# LCD.net
KiCad netlist of a schematic drawn in Altium Designer
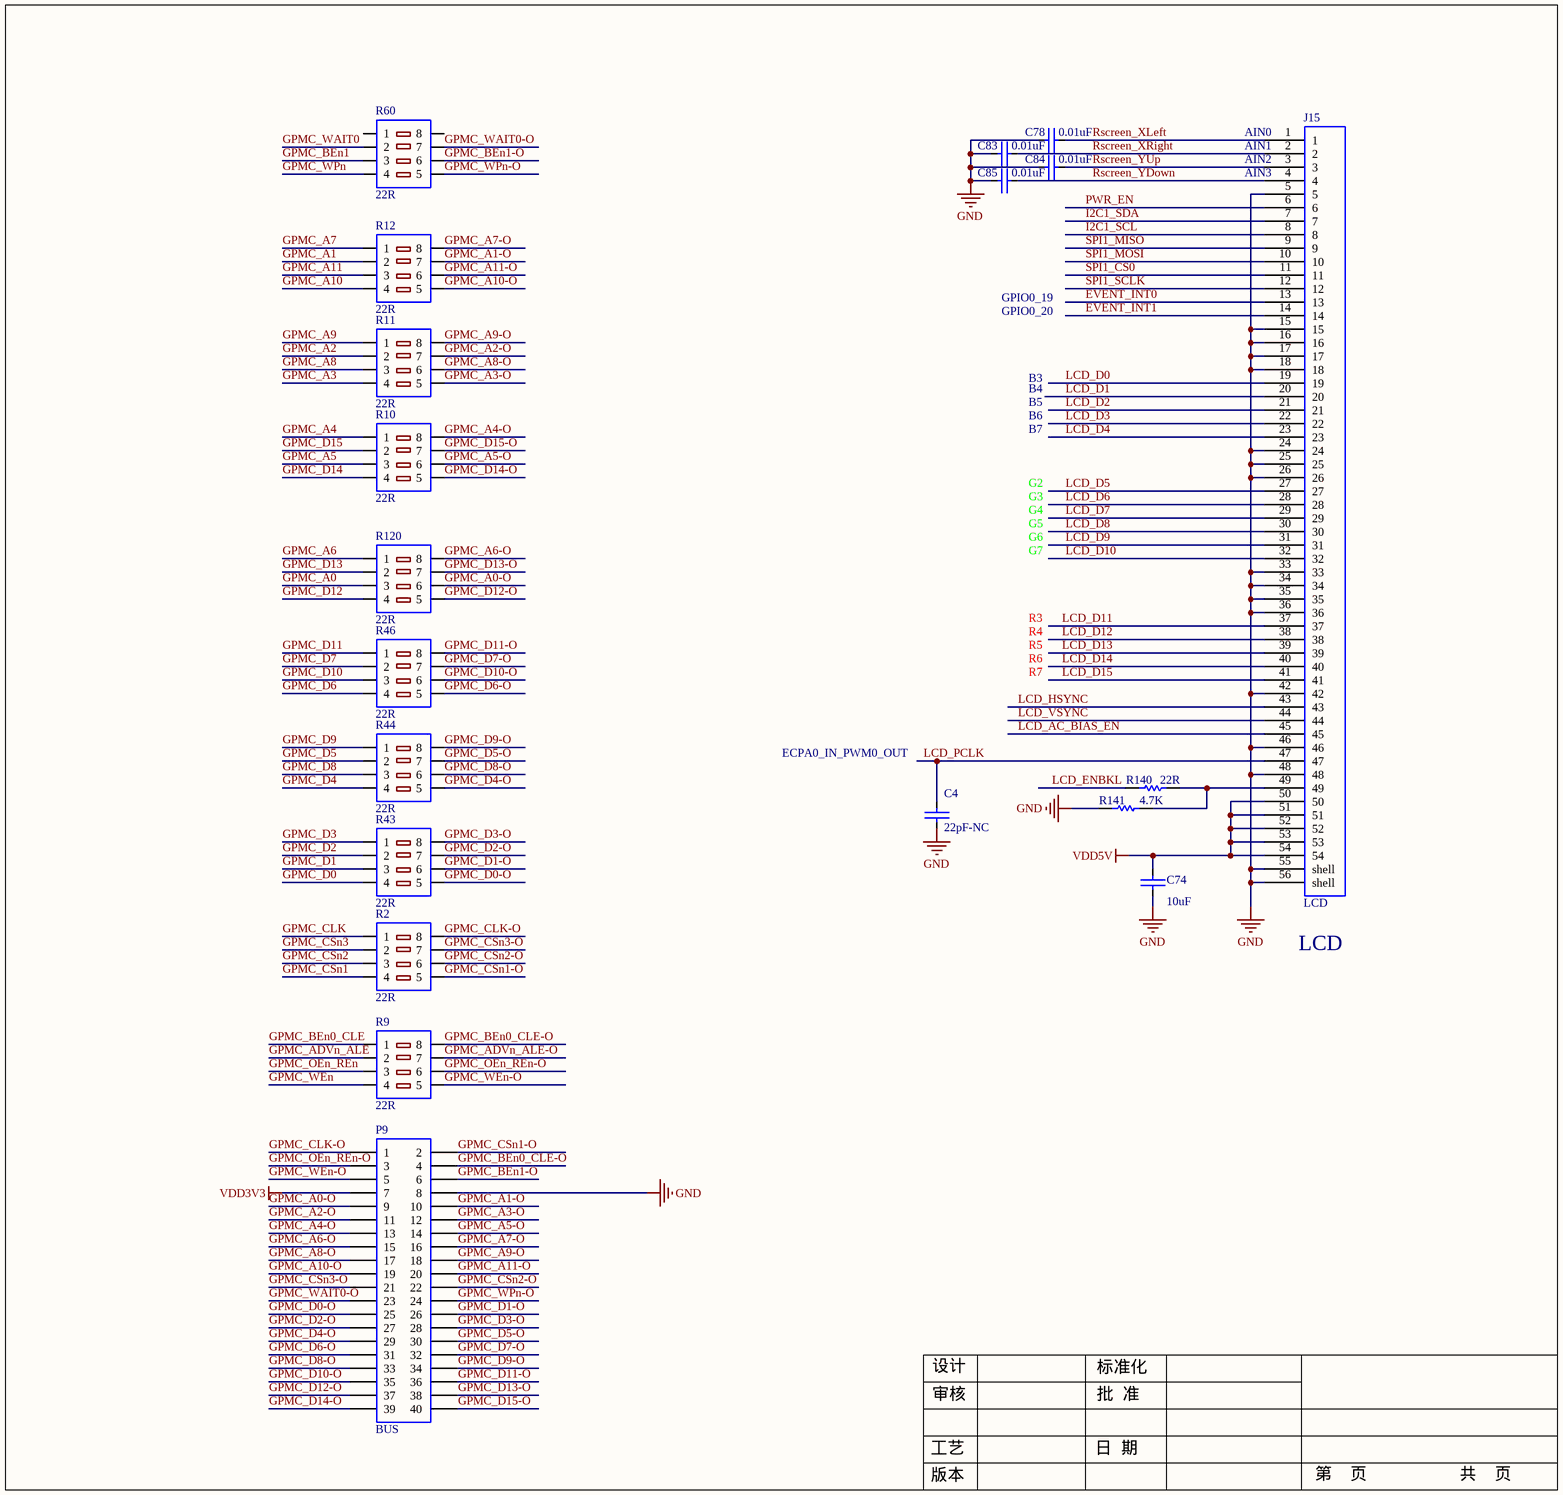
[diagram p0: LCD.SchDoc]

(export (version "E")
  (design (tool "Eeschema 10.0.6"))
  (components
    (comp (ref "C4") (value "22pF-NC") (footprint "C0603_M1608") (libsource (lib "OK335xD") (part "CAP_1")))
    (comp (ref "C74") (value "10uF") (footprint "C0603_M1608") (libsource (lib "OK335xD") (part "CAP_1")))
    (comp (ref "C78") (value "0.01uF") (footprint "C0603_M1608") (libsource (lib "OK335xD") (part "CAP_1")))
    (comp (ref "C83") (value "0.01uF") (footprint "C0603_M1608") (libsource (lib "OK335xD") (part "CAP_1")))
    (comp (ref "C84") (value "0.01uF") (footprint "C0603_M1608") (libsource (lib "OK335xD") (part "CAP_1")))
    (comp (ref "C85") (value "0.01uF") (footprint "C0603_M1608") (libsource (lib "OK335xD") (part "CAP_1")))
    (comp (ref "J15") (value "LCD") (footprint "FPC54") (libsource (lib "OK335xD") (part "FPC54")))
    (comp (ref "P9")
      (value "BUS")
      (description "Header, 20-Pin, Dual row")
      (fields (field (name "PUBLISHER") "Altium Limited"))
      (libsource (lib "OK335xD") (part "Header 20X2"))
    )
    (comp (ref "R2") (value "22R") (footprint "R0603-8P4R") (libsource (lib "OK335xD") (part "8P4R")))
    (comp (ref "R9") (value "22R") (footprint "R0603-8P4R") (libsource (lib "OK335xD") (part "8P4R")))
    (comp (ref "R10") (value "22R") (footprint "R0603-8P4R") (libsource (lib "OK335xD") (part "8P4R")))
    (comp (ref "R11") (value "22R") (footprint "R0603-8P4R") (libsource (lib "OK335xD") (part "8P4R")))
    (comp (ref "R12") (value "22R") (footprint "R0603-8P4R") (libsource (lib "OK335xD") (part "8P4R")))
    (comp (ref "R43") (value "22R") (footprint "R0603-8P4R") (libsource (lib "OK335xD") (part "8P4R")))
    (comp (ref "R44") (value "22R") (footprint "R0603-8P4R") (libsource (lib "OK335xD") (part "8P4R")))
    (comp (ref "R46") (value "22R") (footprint "R0603-8P4R") (libsource (lib "OK335xD") (part "8P4R")))
    (comp (ref "R60") (value "22R") (footprint "R0603-8P4R") (libsource (lib "OK335xD") (part "8P4R")))
    (comp (ref "R120") (value "22R") (footprint "R0603-8P4R") (libsource (lib "OK335xD") (part "8P4R")))
    (comp (ref "R140")
      (value "22R")
      (footprint "R0603_M1608")
      (description "R0603")
      (fields (field (name "PUBLISHER") "Altium Limited"))
      (libsource (lib "Miscellaneous Devices") (part "Res1"))
    )
    (comp (ref "R141")
      (value "4.7K")
      (footprint "R0603_M1608")
      (description "R0603")
      (fields (field (name "PUBLISHER") "Altium Limited"))
      (libsource (lib "Miscellaneous Devices") (part "Res1"))
    )
  )
  (nets
    (net (code "1") (name "/EVENT_INT0") (class "Default")
      (node (ref "J15") (pin "13") (pinfunction "13_13") (pintype "passive"))
    )
    (net (code "2") (name "/EVENT_INT1") (class "Default")
      (node (ref "J15") (pin "14") (pinfunction "14_14") (pintype "passive"))
    )
    (net (code "3") (name "/GPMC_A0") (class "Default")
      (node (ref "R120") (pin "3") (pinfunction "3_3") (pintype "passive"))
    )
    (net (code "4") (name "/GPMC_A0-O") (class "Default")
      (node (ref "P9") (pin "9") (pinfunction "9_9") (pintype "passive"))
      (node (ref "R120") (pin "6") (pinfunction "6_6") (pintype "passive"))
    )
    (net (code "5") (name "/GPMC_A1") (class "Default")
      (node (ref "R12") (pin "2") (pinfunction "2_2") (pintype "passive"))
    )
    (net (code "6") (name "/GPMC_A1-O") (class "Default")
      (node (ref "P9") (pin "10") (pinfunction "10_10") (pintype "passive"))
      (node (ref "R12") (pin "7") (pinfunction "7_7") (pintype "passive"))
    )
    (net (code "7") (name "/GPMC_A2") (class "Default")
      (node (ref "R11") (pin "2") (pinfunction "2_2") (pintype "passive"))
    )
    (net (code "8") (name "/GPMC_A2-O") (class "Default")
      (node (ref "P9") (pin "11") (pinfunction "11_11") (pintype "passive"))
      (node (ref "R11") (pin "7") (pinfunction "7_7") (pintype "passive"))
    )
    (net (code "9") (name "/GPMC_A3") (class "Default")
      (node (ref "R11") (pin "4") (pinfunction "4_4") (pintype "passive"))
    )
    (net (code "10") (name "/GPMC_A3-O") (class "Default")
      (node (ref "P9") (pin "12") (pinfunction "12_12") (pintype "passive"))
      (node (ref "R11") (pin "5") (pinfunction "5_5") (pintype "passive"))
    )
    (net (code "11") (name "/GPMC_A4") (class "Default")
      (node (ref "R10") (pin "1") (pinfunction "1_1") (pintype "passive"))
    )
    (net (code "12") (name "/GPMC_A4-O") (class "Default")
      (node (ref "P9") (pin "13") (pinfunction "13_13") (pintype "passive"))
      (node (ref "R10") (pin "8") (pinfunction "8_8") (pintype "passive"))
    )
    (net (code "13") (name "/GPMC_A5") (class "Default")
      (node (ref "R10") (pin "3") (pinfunction "3_3") (pintype "passive"))
    )
    (net (code "14") (name "/GPMC_A5-O") (class "Default")
      (node (ref "P9") (pin "14") (pinfunction "14_14") (pintype "passive"))
      (node (ref "R10") (pin "6") (pinfunction "6_6") (pintype "passive"))
    )
    (net (code "15") (name "/GPMC_A6") (class "Default")
      (node (ref "R120") (pin "1") (pinfunction "1_1") (pintype "passive"))
    )
    (net (code "16") (name "/GPMC_A6-O") (class "Default")
      (node (ref "P9") (pin "15") (pinfunction "15_15") (pintype "passive"))
      (node (ref "R120") (pin "8") (pinfunction "8_8") (pintype "passive"))
    )
    (net (code "17") (name "/GPMC_A7") (class "Default")
      (node (ref "R12") (pin "1") (pinfunction "1_1") (pintype "passive"))
    )
    (net (code "18") (name "/GPMC_A7-O") (class "Default")
      (node (ref "P9") (pin "16") (pinfunction "16_16") (pintype "passive"))
      (node (ref "R12") (pin "8") (pinfunction "8_8") (pintype "passive"))
    )
    (net (code "19") (name "/GPMC_A8") (class "Default")
      (node (ref "R11") (pin "3") (pinfunction "3_3") (pintype "passive"))
    )
    (net (code "20") (name "/GPMC_A8-O") (class "Default")
      (node (ref "P9") (pin "17") (pinfunction "17_17") (pintype "passive"))
      (node (ref "R11") (pin "6") (pinfunction "6_6") (pintype "passive"))
    )
    (net (code "21") (name "/GPMC_A9") (class "Default")
      (node (ref "R11") (pin "1") (pinfunction "1_1") (pintype "passive"))
    )
    (net (code "22") (name "/GPMC_A9-O") (class "Default")
      (node (ref "P9") (pin "18") (pinfunction "18_18") (pintype "passive"))
      (node (ref "R11") (pin "8") (pinfunction "8_8") (pintype "passive"))
    )
    (net (code "23") (name "/GPMC_A10") (class "Default")
      (node (ref "R12") (pin "4") (pinfunction "4_4") (pintype "passive"))
    )
    (net (code "24") (name "/GPMC_A10-O") (class "Default")
      (node (ref "P9") (pin "19") (pinfunction "19_19") (pintype "passive"))
      (node (ref "R12") (pin "5") (pinfunction "5_5") (pintype "passive"))
    )
    (net (code "25") (name "/GPMC_A11") (class "Default")
      (node (ref "R12") (pin "3") (pinfunction "3_3") (pintype "passive"))
    )
    (net (code "26") (name "/GPMC_A11-O") (class "Default")
      (node (ref "P9") (pin "20") (pinfunction "20_20") (pintype "passive"))
      (node (ref "R12") (pin "6") (pinfunction "6_6") (pintype "passive"))
    )
    (net (code "27") (name "/GPMC_ADVn_ALE") (class "Default")
      (node (ref "R9") (pin "2") (pinfunction "2_2") (pintype "passive"))
    )
    (net (code "28") (name "/GPMC_ADVn_ALE-O") (class "Default")
      (node (ref "R9") (pin "7") (pinfunction "7_7") (pintype "passive"))
    )
    (net (code "29") (name "/GPMC_BEn0_CLE") (class "Default")
      (node (ref "R9") (pin "1") (pinfunction "1_1") (pintype "passive"))
    )
    (net (code "30") (name "/GPMC_BEn0_CLE-O") (class "Default")
      (node (ref "P9") (pin "4") (pinfunction "4_4") (pintype "passive"))
      (node (ref "R9") (pin "8") (pinfunction "8_8") (pintype "passive"))
    )
    (net (code "31") (name "/GPMC_BEn1") (class "Default")
      (node (ref "R60") (pin "3") (pinfunction "3_3") (pintype "passive"))
    )
    (net (code "32") (name "/GPMC_BEn1-O") (class "Default")
      (node (ref "P9") (pin "6") (pinfunction "6_6") (pintype "passive"))
      (node (ref "R60") (pin "6") (pinfunction "6_6") (pintype "passive"))
    )
    (net (code "33") (name "/GPMC_CLK") (class "Default")
      (node (ref "R2") (pin "1") (pinfunction "1_1") (pintype "passive"))
    )
    (net (code "34") (name "/GPMC_CLK-O") (class "Default")
      (node (ref "P9") (pin "1") (pinfunction "1_1") (pintype "passive"))
      (node (ref "R2") (pin "8") (pinfunction "8_8") (pintype "passive"))
    )
    (net (code "35") (name "/GPMC_CSn1") (class "Default")
      (node (ref "R2") (pin "4") (pinfunction "4_4") (pintype "passive"))
    )
    (net (code "36") (name "/GPMC_CSn1-O") (class "Default")
      (node (ref "P9") (pin "2") (pinfunction "2_2") (pintype "passive"))
      (node (ref "R2") (pin "5") (pinfunction "5_5") (pintype "passive"))
    )
    (net (code "37") (name "/GPMC_CSn2") (class "Default")
      (node (ref "R2") (pin "3") (pinfunction "3_3") (pintype "passive"))
    )
    (net (code "38") (name "/GPMC_CSn2-O") (class "Default")
      (node (ref "P9") (pin "22") (pinfunction "22_22") (pintype "passive"))
      (node (ref "R2") (pin "6") (pinfunction "6_6") (pintype "passive"))
    )
    (net (code "39") (name "/GPMC_CSn3") (class "Default")
      (node (ref "R2") (pin "2") (pinfunction "2_2") (pintype "passive"))
    )
    (net (code "40") (name "/GPMC_CSn3-O") (class "Default")
      (node (ref "P9") (pin "21") (pinfunction "21_21") (pintype "passive"))
      (node (ref "R2") (pin "7") (pinfunction "7_7") (pintype "passive"))
    )
    (net (code "41") (name "/GPMC_D0") (class "Default")
      (node (ref "R43") (pin "4") (pinfunction "4_4") (pintype "passive"))
    )
    (net (code "42") (name "/GPMC_D0-O") (class "Default")
      (node (ref "P9") (pin "25") (pinfunction "25_25") (pintype "passive"))
      (node (ref "R43") (pin "5") (pinfunction "5_5") (pintype "passive"))
    )
    (net (code "43") (name "/GPMC_D1") (class "Default")
      (node (ref "R43") (pin "3") (pinfunction "3_3") (pintype "passive"))
    )
    (net (code "44") (name "/GPMC_D1-O") (class "Default")
      (node (ref "P9") (pin "26") (pinfunction "26_26") (pintype "passive"))
      (node (ref "R43") (pin "6") (pinfunction "6_6") (pintype "passive"))
    )
    (net (code "45") (name "/GPMC_D2") (class "Default")
      (node (ref "R43") (pin "2") (pinfunction "2_2") (pintype "passive"))
    )
    (net (code "46") (name "/GPMC_D2-O") (class "Default")
      (node (ref "P9") (pin "27") (pinfunction "27_27") (pintype "passive"))
      (node (ref "R43") (pin "7") (pinfunction "7_7") (pintype "passive"))
    )
    (net (code "47") (name "/GPMC_D3") (class "Default")
      (node (ref "R43") (pin "1") (pinfunction "1_1") (pintype "passive"))
    )
    (net (code "48") (name "/GPMC_D3-O") (class "Default")
      (node (ref "P9") (pin "28") (pinfunction "28_28") (pintype "passive"))
      (node (ref "R43") (pin "8") (pinfunction "8_8") (pintype "passive"))
    )
    (net (code "49") (name "/GPMC_D4") (class "Default")
      (node (ref "R44") (pin "4") (pinfunction "4_4") (pintype "passive"))
    )
    (net (code "50") (name "/GPMC_D4-O") (class "Default")
      (node (ref "P9") (pin "29") (pinfunction "29_29") (pintype "passive"))
      (node (ref "R44") (pin "5") (pinfunction "5_5") (pintype "passive"))
    )
    (net (code "51") (name "/GPMC_D5") (class "Default")
      (node (ref "R44") (pin "2") (pinfunction "2_2") (pintype "passive"))
    )
    (net (code "52") (name "/GPMC_D5-O") (class "Default")
      (node (ref "P9") (pin "30") (pinfunction "30_30") (pintype "passive"))
      (node (ref "R44") (pin "7") (pinfunction "7_7") (pintype "passive"))
    )
    (net (code "53") (name "/GPMC_D6") (class "Default")
      (node (ref "R46") (pin "4") (pinfunction "4_4") (pintype "passive"))
    )
    (net (code "54") (name "/GPMC_D6-O") (class "Default")
      (node (ref "P9") (pin "31") (pinfunction "31_31") (pintype "passive"))
      (node (ref "R46") (pin "5") (pinfunction "5_5") (pintype "passive"))
    )
    (net (code "55") (name "/GPMC_D7") (class "Default")
      (node (ref "R46") (pin "2") (pinfunction "2_2") (pintype "passive"))
    )
    (net (code "56") (name "/GPMC_D7-O") (class "Default")
      (node (ref "P9") (pin "32") (pinfunction "32_32") (pintype "passive"))
      (node (ref "R46") (pin "7") (pinfunction "7_7") (pintype "passive"))
    )
    (net (code "57") (name "/GPMC_D8") (class "Default")
      (node (ref "R44") (pin "3") (pinfunction "3_3") (pintype "passive"))
    )
    (net (code "58") (name "/GPMC_D8-O") (class "Default")
      (node (ref "P9") (pin "33") (pinfunction "33_33") (pintype "passive"))
      (node (ref "R44") (pin "6") (pinfunction "6_6") (pintype "passive"))
    )
    (net (code "59") (name "/GPMC_D9") (class "Default")
      (node (ref "R44") (pin "1") (pinfunction "1_1") (pintype "passive"))
    )
    (net (code "60") (name "/GPMC_D9-O") (class "Default")
      (node (ref "P9") (pin "34") (pinfunction "34_34") (pintype "passive"))
      (node (ref "R44") (pin "8") (pinfunction "8_8") (pintype "passive"))
    )
    (net (code "61") (name "/GPMC_D10") (class "Default")
      (node (ref "R46") (pin "3") (pinfunction "3_3") (pintype "passive"))
    )
    (net (code "62") (name "/GPMC_D10-O") (class "Default")
      (node (ref "P9") (pin "35") (pinfunction "35_35") (pintype "passive"))
      (node (ref "R46") (pin "6") (pinfunction "6_6") (pintype "passive"))
    )
    (net (code "63") (name "/GPMC_D11") (class "Default")
      (node (ref "R46") (pin "1") (pinfunction "1_1") (pintype "passive"))
    )
    (net (code "64") (name "/GPMC_D11-O") (class "Default")
      (node (ref "P9") (pin "36") (pinfunction "36_36") (pintype "passive"))
      (node (ref "R46") (pin "8") (pinfunction "8_8") (pintype "passive"))
    )
    (net (code "65") (name "/GPMC_D12") (class "Default")
      (node (ref "R120") (pin "4") (pinfunction "4_4") (pintype "passive"))
    )
    (net (code "66") (name "/GPMC_D12-O") (class "Default")
      (node (ref "P9") (pin "37") (pinfunction "37_37") (pintype "passive"))
      (node (ref "R120") (pin "5") (pinfunction "5_5") (pintype "passive"))
    )
    (net (code "67") (name "/GPMC_D13") (class "Default")
      (node (ref "R120") (pin "2") (pinfunction "2_2") (pintype "passive"))
    )
    (net (code "68") (name "/GPMC_D13-O") (class "Default")
      (node (ref "P9") (pin "38") (pinfunction "38_38") (pintype "passive"))
      (node (ref "R120") (pin "7") (pinfunction "7_7") (pintype "passive"))
    )
    (net (code "69") (name "/GPMC_D14") (class "Default")
      (node (ref "R10") (pin "4") (pinfunction "4_4") (pintype "passive"))
    )
    (net (code "70") (name "/GPMC_D14-O") (class "Default")
      (node (ref "P9") (pin "39") (pinfunction "39_39") (pintype "passive"))
      (node (ref "R10") (pin "5") (pinfunction "5_5") (pintype "passive"))
    )
    (net (code "71") (name "/GPMC_D15") (class "Default")
      (node (ref "R10") (pin "2") (pinfunction "2_2") (pintype "passive"))
    )
    (net (code "72") (name "/GPMC_D15-O") (class "Default")
      (node (ref "P9") (pin "40") (pinfunction "40_40") (pintype "passive"))
      (node (ref "R10") (pin "7") (pinfunction "7_7") (pintype "passive"))
    )
    (net (code "73") (name "/GPMC_OEn_REn") (class "Default")
      (node (ref "R9") (pin "3") (pinfunction "3_3") (pintype "passive"))
    )
    (net (code "74") (name "/GPMC_OEn_REn-O") (class "Default")
      (node (ref "P9") (pin "3") (pinfunction "3_3") (pintype "passive"))
      (node (ref "R9") (pin "6") (pinfunction "6_6") (pintype "passive"))
    )
    (net (code "75") (name "/GPMC_WAIT0") (class "Default")
      (node (ref "R60") (pin "2") (pinfunction "2_2") (pintype "passive"))
    )
    (net (code "76") (name "/GPMC_WAIT0-O") (class "Default")
      (node (ref "P9") (pin "23") (pinfunction "23_23") (pintype "passive"))
      (node (ref "R60") (pin "7") (pinfunction "7_7") (pintype "passive"))
    )
    (net (code "77") (name "/GPMC_WEn") (class "Default")
      (node (ref "R9") (pin "4") (pinfunction "4_4") (pintype "passive"))
    )
    (net (code "78") (name "/GPMC_WEn-O") (class "Default")
      (node (ref "P9") (pin "5") (pinfunction "5_5") (pintype "passive"))
      (node (ref "R9") (pin "5") (pinfunction "5_5") (pintype "passive"))
    )
    (net (code "79") (name "/GPMC_WPn") (class "Default")
      (node (ref "R60") (pin "4") (pinfunction "4_4") (pintype "passive"))
    )
    (net (code "80") (name "/GPMC_WPn-O") (class "Default")
      (node (ref "P9") (pin "24") (pinfunction "24_24") (pintype "passive"))
      (node (ref "R60") (pin "5") (pinfunction "5_5") (pintype "passive"))
    )
    (net (code "81") (name "/I2C1_SCL") (class "Default")
      (node (ref "J15") (pin "8") (pinfunction "8_8") (pintype "passive"))
    )
    (net (code "82") (name "/I2C1_SDA") (class "Default")
      (node (ref "J15") (pin "7") (pinfunction "7_7") (pintype "passive"))
    )
    (net (code "83") (name "/LCD_AC_BIAS_EN") (class "Default")
      (node (ref "J15") (pin "45") (pinfunction "45_45") (pintype "passive"))
    )
    (net (code "84") (name "/LCD_D0") (class "Default")
      (node (ref "J15") (pin "19") (pinfunction "19_19") (pintype "passive"))
    )
    (net (code "85") (name "/LCD_D1") (class "Default")
      (node (ref "J15") (pin "20") (pinfunction "20_20") (pintype "passive"))
    )
    (net (code "86") (name "/LCD_D2") (class "Default")
      (node (ref "J15") (pin "21") (pinfunction "21_21") (pintype "passive"))
    )
    (net (code "87") (name "/LCD_D3") (class "Default")
      (node (ref "J15") (pin "22") (pinfunction "22_22") (pintype "passive"))
    )
    (net (code "88") (name "/LCD_D4") (class "Default")
      (node (ref "J15") (pin "23") (pinfunction "23_23") (pintype "passive"))
    )
    (net (code "89") (name "/LCD_D5") (class "Default")
      (node (ref "J15") (pin "27") (pinfunction "27_27") (pintype "passive"))
    )
    (net (code "90") (name "/LCD_D6") (class "Default")
      (node (ref "J15") (pin "28") (pinfunction "28_28") (pintype "passive"))
    )
    (net (code "91") (name "/LCD_D7") (class "Default")
      (node (ref "J15") (pin "29") (pinfunction "29_29") (pintype "passive"))
    )
    (net (code "92") (name "/LCD_D8") (class "Default")
      (node (ref "J15") (pin "30") (pinfunction "30_30") (pintype "passive"))
    )
    (net (code "93") (name "/LCD_D9") (class "Default")
      (node (ref "J15") (pin "31") (pinfunction "31_31") (pintype "passive"))
    )
    (net (code "94") (name "/LCD_D10") (class "Default")
      (node (ref "J15") (pin "32") (pinfunction "32_32") (pintype "passive"))
    )
    (net (code "95") (name "/LCD_D11") (class "Default")
      (node (ref "J15") (pin "37") (pinfunction "37_37") (pintype "passive"))
    )
    (net (code "96") (name "/LCD_D12") (class "Default")
      (node (ref "J15") (pin "38") (pinfunction "38_38") (pintype "passive"))
    )
    (net (code "97") (name "/LCD_D13") (class "Default")
      (node (ref "J15") (pin "39") (pinfunction "39_39") (pintype "passive"))
    )
    (net (code "98") (name "/LCD_D14") (class "Default")
      (node (ref "J15") (pin "40") (pinfunction "40_40") (pintype "passive"))
    )
    (net (code "99") (name "/LCD_D15") (class "Default")
      (node (ref "J15") (pin "41") (pinfunction "41_41") (pintype "passive"))
    )
    (net (code "100") (name "/LCD_ENBKL") (class "Default")
      (node (ref "R140") (pin "1") (pinfunction "1_1") (pintype "passive"))
    )
    (net (code "101") (name "/LCD_HSYNC") (class "Default")
      (node (ref "J15") (pin "43") (pinfunction "43_43") (pintype "passive"))
    )
    (net (code "102") (name "/LCD_PCLK") (class "Default")
      (node (ref "C4") (pin "2") (pintype "passive"))
      (node (ref "J15") (pin "47") (pinfunction "47_47") (pintype "passive"))
    )
    (net (code "103") (name "/LCD_VSYNC") (class "Default")
      (node (ref "J15") (pin "44") (pinfunction "44_44") (pintype "passive"))
    )
    (net (code "104") (name "/PWR_EN") (class "Default")
      (node (ref "J15") (pin "6") (pinfunction "6_6") (pintype "passive"))
    )
    (net (code "105") (name "/Rscreen_XLeft") (class "Default")
      (node (ref "C78") (pin "1") (pintype "passive"))
      (node (ref "J15") (pin "1") (pinfunction "1_1") (pintype "passive"))
    )
    (net (code "106") (name "/Rscreen_XRight") (class "Default")
      (node (ref "C83") (pin "1") (pintype "passive"))
      (node (ref "J15") (pin "2") (pinfunction "2_2") (pintype "passive"))
    )
    (net (code "107") (name "/Rscreen_YDown") (class "Default")
      (node (ref "C85") (pin "1") (pintype "passive"))
      (node (ref "J15") (pin "4") (pinfunction "4_4") (pintype "passive"))
    )
    (net (code "108") (name "/Rscreen_YUp") (class "Default")
      (node (ref "C84") (pin "1") (pintype "passive"))
      (node (ref "J15") (pin "3") (pinfunction "3_3") (pintype "passive"))
    )
    (net (code "109") (name "/SPI1_CS0") (class "Default")
      (node (ref "J15") (pin "11") (pinfunction "11_11") (pintype "passive"))
    )
    (net (code "110") (name "/SPI1_MISO") (class "Default")
      (node (ref "J15") (pin "9") (pinfunction "9_9") (pintype "passive"))
    )
    (net (code "111") (name "/SPI1_MOSI") (class "Default")
      (node (ref "J15") (pin "10") (pinfunction "10_10") (pintype "passive"))
    )
    (net (code "112") (name "/SPI1_SCLK") (class "Default")
      (node (ref "J15") (pin "12") (pinfunction "12_12") (pintype "passive"))
    )
    (net (code "113") (name "GND") (class "Default")
      (node (ref "C4") (pin "1") (pintype "passive"))
      (node (ref "C74") (pin "2") (pintype "passive"))
      (node (ref "C78") (pin "2") (pintype "passive"))
      (node (ref "C83") (pin "2") (pintype "passive"))
      (node (ref "C84") (pin "2") (pintype "passive"))
      (node (ref "C85") (pin "2") (pintype "passive"))
      (node (ref "J15") (pin "15") (pinfunction "15_15") (pintype "passive"))
      (node (ref "J15") (pin "16") (pinfunction "16_16") (pintype "passive"))
      (node (ref "J15") (pin "17") (pinfunction "17_17") (pintype "passive"))
      (node (ref "J15") (pin "18") (pinfunction "18_18") (pintype "passive"))
      (node (ref "J15") (pin "24") (pinfunction "24_24") (pintype "passive"))
      (node (ref "J15") (pin "25") (pinfunction "25_25") (pintype "passive"))
      (node (ref "J15") (pin "26") (pinfunction "26_26") (pintype "passive"))
      (node (ref "J15") (pin "33") (pinfunction "33_33") (pintype "passive"))
      (node (ref "J15") (pin "34") (pinfunction "34_34") (pintype "passive"))
      (node (ref "J15") (pin "35") (pinfunction "35_35") (pintype "passive"))
      (node (ref "J15") (pin "36") (pinfunction "36_36") (pintype "passive"))
      (node (ref "J15") (pin "42") (pinfunction "42_42") (pintype "passive"))
      (node (ref "J15") (pin "46") (pinfunction "46_46") (pintype "passive"))
      (node (ref "J15") (pin "48") (pinfunction "48_48") (pintype "passive"))
      (node (ref "J15") (pin "5") (pinfunction "5_5") (pintype "passive"))
      (node (ref "J15") (pin "55") (pinfunction "shell_55") (pintype "passive"))
      (node (ref "J15") (pin "56") (pinfunction "shell_56") (pintype "passive"))
      (node (ref "P9") (pin "8") (pinfunction "8_8") (pintype "passive"))
      (node (ref "R141") (pin "1") (pinfunction "1_1") (pintype "passive"))
    )
    (net (code "114") (name "Net-(J15-Pad49)") (class "Default")
      (node (ref "J15") (pin "49") (pinfunction "49_49") (pintype "passive"))
      (node (ref "R140") (pin "2") (pinfunction "2_2") (pintype "passive"))
      (node (ref "R141") (pin "2") (pinfunction "2_2") (pintype "passive"))
    )
    (net (code "115") (name "VDD3V3") (class "Default")
      (node (ref "P9") (pin "7") (pinfunction "7_7") (pintype "passive"))
    )
    (net (code "116") (name "VDD5V") (class "Default")
      (node (ref "C74") (pin "1") (pintype "passive"))
      (node (ref "J15") (pin "50") (pinfunction "50_50") (pintype "passive"))
      (node (ref "J15") (pin "51") (pinfunction "51_51") (pintype "passive"))
      (node (ref "J15") (pin "52") (pinfunction "52_52") (pintype "passive"))
      (node (ref "J15") (pin "53") (pinfunction "53_53") (pintype "passive"))
      (node (ref "J15") (pin "54") (pinfunction "54_54") (pintype "passive"))
    )
    (net (code "117") (name "unconnected-(R60-Pad1)") (class "Default")
      (node (ref "R60") (pin "1") (pinfunction "1_1") (pintype "passive"))
    )
    (net (code "118") (name "unconnected-(R60-Pad8)") (class "Default")
      (node (ref "R60") (pin "8") (pinfunction "8_8") (pintype "passive"))
    )
  )
)
